# Esquematico_Fonte.net
KiCad netlist of a schematic drawn in Altium Designer
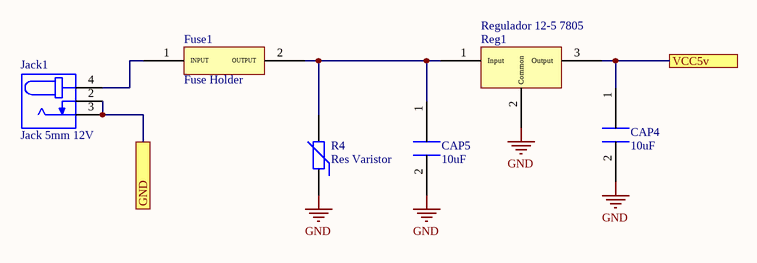
[diagram p0: Esquematico_Fonte.SchDoc]

(export (version "E")
  (design (tool "Eeschema 10.0.6"))
  (components
    (comp (ref "CAP4")
      (value "10uF")
      (footprint "Capacitor Eletro")
      (description "Condensador")
      (libsource (lib "myLibAltium") (part "33pF"))
    )
    (comp (ref "CAP5")
      (value "10uF")
      (footprint "Capacitor Eletro")
      (description "Condensador")
      (libsource (lib "myLibAltium") (part "33pF"))
    )
    (comp (ref "Fuse1")
      (value "Fuse Holder")
      (footprint "Fuse Holder")
      (libsource (lib "myLibAltium") (part "Fuse Holder"))
    )
    (comp (ref "Jack1")
      (value "Jack 5mm 12V")
      (footprint "Jack 5mm")
      (libsource (lib "myLibAltium") (part "Jack 5mm 12V"))
    )
    (comp (ref "R4")
      (value "Res Varistor")
      (footprint "6-0805_N")
      (description "Varistor (Voltage-Sensitive Resistor)")
      (fields (field (name "PUBLISHER") "Altium Limited"))
      (libsource (lib "Miscellaneous Devices") (part "Res Varistor"))
    )
    (comp (ref "Reg1")
      (value "Regulador 12-5 7805")
      (footprint "Regulador 12-5 7805")
      (libsource (lib "myLibAltium") (part "Regulador 12-5 7805"))
    )
  )
  (nets
    (net (code "1") (name "/VCC5v") (class "Default")
      (node (ref "CAP4") (pin "1") (pintype "passive"))
      (node (ref "Reg1") (pin "3") (pinfunction "Output_3") (pintype "passive"))
    )
    (net (code "2") (name "GND") (class "Default")
      (node (ref "CAP4") (pin "2") (pintype "passive"))
      (node (ref "CAP5") (pin "2") (pintype "passive"))
      (node (ref "Jack1") (pin "2") (pinfunction "4_2") (pintype "passive"))
      (node (ref "Jack1") (pin "3") (pinfunction "5_3") (pintype "passive"))
      (node (ref "R4") (pin "1") (pinfunction "1_1") (pintype "passive"))
      (node (ref "Reg1") (pin "2") (pinfunction "Common_2") (pintype "passive"))
    )
    (net (code "3") (name "Net-(Fuse1-INPUT)") (class "Default")
      (node (ref "Fuse1") (pin "1") (pinfunction "INPUT_1") (pintype "passive"))
      (node (ref "Jack1") (pin "4") (pinfunction "2_4") (pintype "passive"))
    )
    (net (code "4") (name "Net-(Fuse1-OUTPUT)") (class "Default")
      (node (ref "CAP5") (pin "1") (pintype "passive"))
      (node (ref "Fuse1") (pin "2") (pinfunction "OUTPUT_2") (pintype "passive"))
      (node (ref "R4") (pin "2") (pinfunction "2_2") (pintype "passive"))
      (node (ref "Reg1") (pin "1") (pinfunction "Input_1") (pintype "passive"))
    )
  )
)
